# 4_-_Ethernet_PHY.net
KiCad netlist of a schematic drawn in Altium Designer
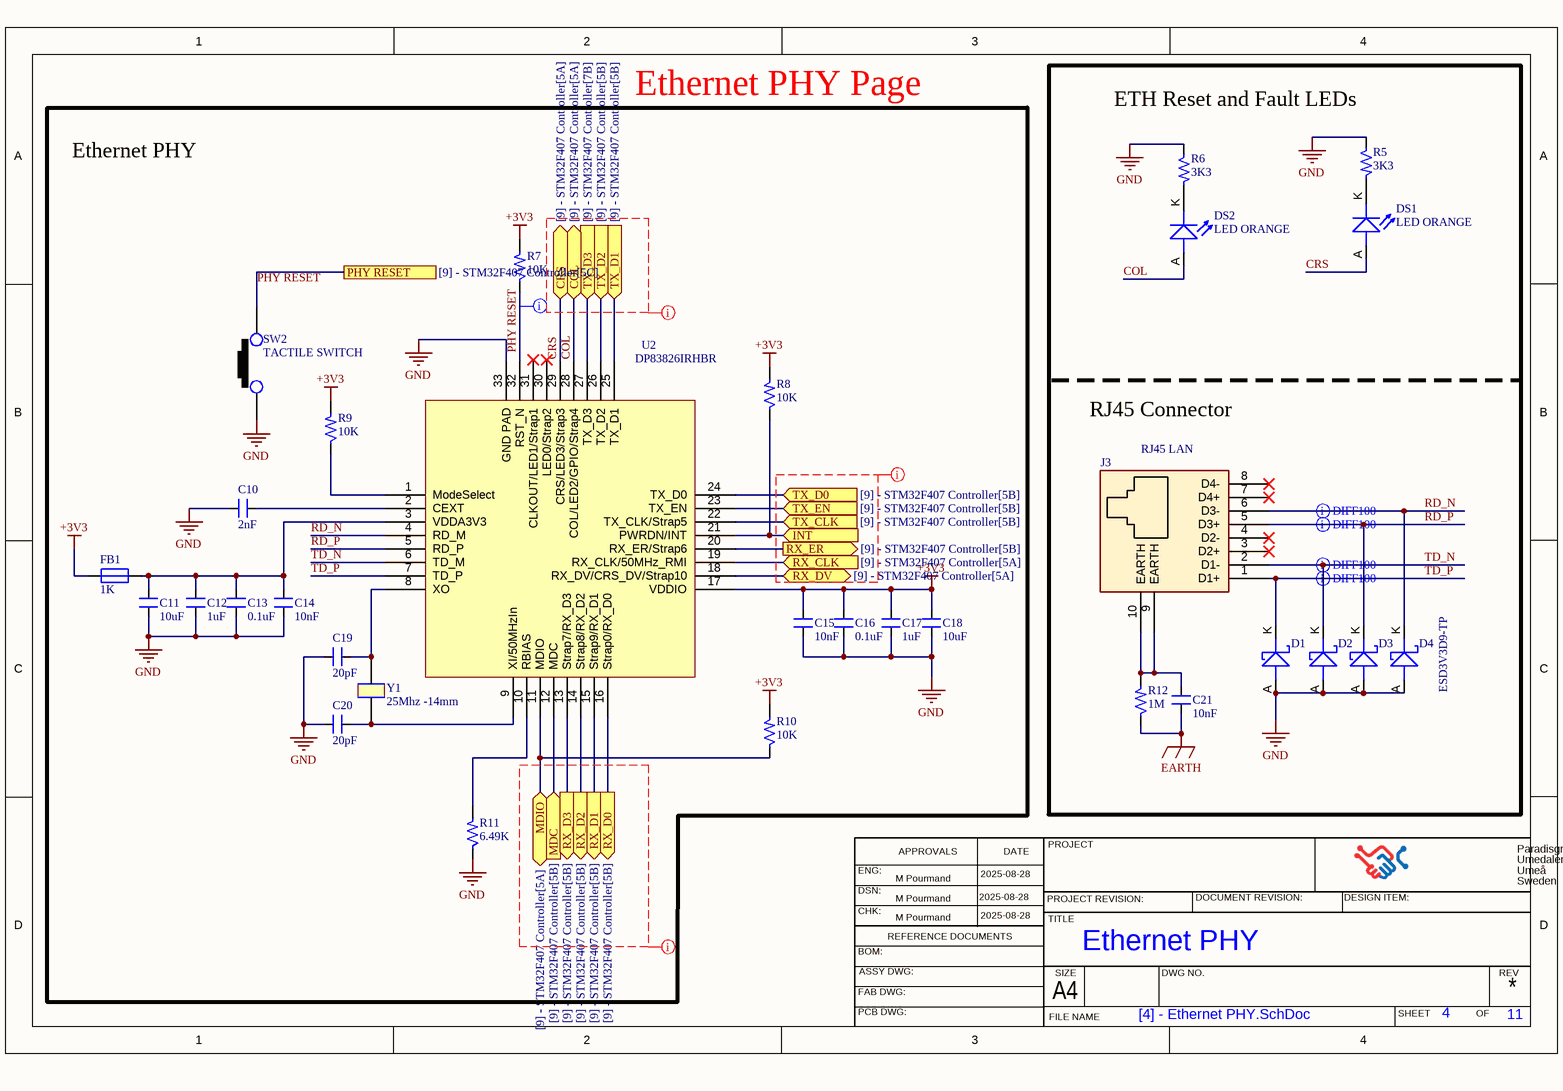
[diagram p0: [4] - Ethernet PHY.SchDoc]

(export (version "E")
  (design (tool "Eeschema 10.0.6"))
  (components
    (comp (ref "C10")
      (value "2nF")
      (footprint "CAP_0805")
      (description "2000pF ±10% 50V Ceramic Capacitor X7R 0805 (2012 Metric)")
      (fields
        (field (name "MANUFACTURER") "Samsung Electro-Mechanics")
        (field (name "MANUFACTURER PART NUMBER") "CL21B202KBANNNC")
      )
      (libsource (lib "ESTEEMPCBLIB") (part "CAP_2nF-50V-10%-0805"))
    )
    (comp (ref "C11")
      (value "10uF")
      (footprint "CAP_1206")
      (description "10µF ±10% 50V Ceramic Capacitor X7R 1206 (3216 Metric)")
      (fields
        (field (name "MANUFACTURER") "KEMET")
        (field (name "MANUFACTURER PART NUMBER") "CL31B106KBHNNNE")
      )
      (libsource (lib "ESTEEMPCBLIB") (part "CAP_10uF-50V-10%-1206"))
    )
    (comp (ref "C12")
      (value "1uF")
      (footprint "CAP_0805")
      (description "1µF ±5% 50V Ceramic Capacitor X7R 0805 (2012 Metric)")
      (fields
        (field (name "MANUFACTURER") "Samsung")
        (field (name "MANUFACTURER PART NUMBER") "CC0805JKX7R9BB105")
      )
      (libsource (lib "ESTEEMPCBLIB") (part "CAP_1uF-50V-5%-0805"))
    )
    (comp (ref "C13")
      (value "0.1uF")
      (footprint "CAP_0805")
      (description "0.1µF ±10% 50V Ceramic Capacitor X7R 0805 (2012 Metric)")
      (fields
        (field (name "MANUFACTURER") "Samsung")
        (field (name "MANUFACTURER PART NUMBER") "CL21B104KBCNNNC")
      )
      (libsource (lib "ESTEEMPCBLIB") (part "CAP_0.1uF-50V-10%-0805"))
    )
    (comp (ref "C14")
      (value "10nF")
      (footprint "CAP_0805")
      (description "10000pF ±10% 50V Ceramic Capacitor X7R 0805 (2012 Metric)")
      (fields
        (field (name "MANUFACTURER") "Samsung")
        (field (name "MANUFACTURER PART NUMBER") "C0805C103K5RECAUTO")
      )
      (libsource (lib "ESTEEMPCBLIB") (part "CAP_10nF-50V-10%-0805"))
    )
    (comp (ref "C15")
      (value "10nF")
      (footprint "CAP_0805")
      (description "10000pF ±10% 50V Ceramic Capacitor X7R 0805 (2012 Metric)")
      (fields
        (field (name "MANUFACTURER") "Samsung")
        (field (name "MANUFACTURER PART NUMBER") "C0805C103K5RECAUTO")
      )
      (libsource (lib "ESTEEMPCBLIB") (part "CAP_10nF-50V-10%-0805"))
    )
    (comp (ref "C16")
      (value "0.1uF")
      (footprint "CAP_0805")
      (description "0.1µF ±10% 50V Ceramic Capacitor X7R 0805 (2012 Metric)")
      (fields
        (field (name "MANUFACTURER") "Samsung")
        (field (name "MANUFACTURER PART NUMBER") "CL21B104KBCNNNC")
      )
      (libsource (lib "ESTEEMPCBLIB") (part "CAP_0.1uF-50V-10%-0805"))
    )
    (comp (ref "C17")
      (value "1uF")
      (footprint "CAP_0805")
      (description "1µF ±5% 50V Ceramic Capacitor X7R 0805 (2012 Metric)")
      (fields
        (field (name "MANUFACTURER") "Samsung")
        (field (name "MANUFACTURER PART NUMBER") "CC0805JKX7R9BB105")
      )
      (libsource (lib "ESTEEMPCBLIB") (part "CAP_1uF-50V-5%-0805"))
    )
    (comp (ref "C18")
      (value "10uF")
      (footprint "CAP_1206")
      (description "10µF ±10% 50V Ceramic Capacitor X7R 1206 (3216 Metric)")
      (fields
        (field (name "MANUFACTURER") "KEMET")
        (field (name "MANUFACTURER PART NUMBER") "CL31B106KBHNNNE")
      )
      (libsource (lib "ESTEEMPCBLIB") (part "CAP_10uF-50V-10%-1206"))
    )
    (comp (ref "C19")
      (value "20pF")
      (footprint "CAP_0805")
      (description "±10% 50V Ceramic Capacitor C0G, NP0 0805 (2012 Metric)")
      (fields
        (field (name "MANUFACTURER") "AVX Corporation")
        (field (name "MANUFACTURER PART NUMBER") "08055A200KAT2A")
      )
      (libsource (lib "ESTEEMPCBLIB") (part "CAP_20pF-50V-10%-0805"))
    )
    (comp (ref "C20")
      (value "20pF")
      (footprint "CAP_0805")
      (description "±10% 50V Ceramic Capacitor C0G, NP0 0805 (2012 Metric)")
      (fields
        (field (name "MANUFACTURER") "AVX Corporation")
        (field (name "MANUFACTURER PART NUMBER") "08055A200KAT2A")
      )
      (libsource (lib "ESTEEMPCBLIB") (part "CAP_20pF-50V-10%-0805"))
    )
    (comp (ref "C21")
      (value "10nF")
      (footprint "CAP_P196_102X287_H332_RAD_TH")
      (description "10000pF ±10% 1000V (1kV) Ceramic Capacitor X7R Radial")
      (fields
        (field (name "MANUFACTURER") "Yageo")
        (field (name "MANUFACTURER PART NUMBER") "RDER73A103K2K1H03B")
      )
      (libsource (lib "ESTEEMPCBLIB") (part "CAP_10nF-1KV-10%-RAD-TH"))
    )
    (comp (ref "D1")
      (value "ESD3V3D9-TP")
      (footprint "DIO_SOD-923")
      (description "8.8V Clamp 5A (8/20µs) Ipp Tvs Diode Surface Mount SOD-923")
      (fields (field (name "MANUFACTURER") "Micro Commercial Co"))
      (libsource (lib "ESTEEMPCBLIB") (part "DIO-T_3.3V-8.8V-SOD923"))
    )
    (comp (ref "D2")
      (value "ESD3V3D9-TP")
      (footprint "DIO_SOD-923")
      (description "8.8V Clamp 5A (8/20µs) Ipp Tvs Diode Surface Mount SOD-923")
      (fields (field (name "MANUFACTURER") "Micro Commercial Co"))
      (libsource (lib "ESTEEMPCBLIB") (part "DIO-T_3.3V-8.8V-SOD923"))
    )
    (comp (ref "D3")
      (value "ESD3V3D9-TP")
      (footprint "DIO_SOD-923")
      (description "8.8V Clamp 5A (8/20µs) Ipp Tvs Diode Surface Mount SOD-923")
      (fields (field (name "MANUFACTURER") "Micro Commercial Co"))
      (libsource (lib "ESTEEMPCBLIB") (part "DIO-T_3.3V-8.8V-SOD923"))
    )
    (comp (ref "D4")
      (value "ESD3V3D9-TP")
      (footprint "DIO_SOD-923")
      (description "8.8V Clamp 5A (8/20µs) Ipp Tvs Diode Surface Mount SOD-923")
      (fields (field (name "MANUFACTURER") "Micro Commercial Co"))
      (libsource (lib "ESTEEMPCBLIB") (part "DIO-T_3.3V-8.8V-SOD923"))
    )
    (comp (ref "DS1")
      (value "LED ORANGE")
      (footprint "LED_0805")
      (description "Orange 605nm LED Indication - Discrete 2V 0805 (2012 Metric)")
      (fields
        (field (name "MANUFACTURER") "Vishay Lite-On")
        (field (name "MANUFACTURER PART NUMBER") "LTST-C170KFKT")
      )
      (libsource (lib "ESTEEMPCBLIB") (part "LED_ORANGE-2V-20mA-0805"))
    )
    (comp (ref "DS2")
      (value "LED ORANGE")
      (footprint "LED_0805")
      (description "Orange 605nm LED Indication - Discrete 2V 0805 (2012 Metric)")
      (fields
        (field (name "MANUFACTURER") "Vishay Lite-On")
        (field (name "MANUFACTURER PART NUMBER") "LTST-C170KFKT")
      )
      (libsource (lib "ESTEEMPCBLIB") (part "LED_ORANGE-2V-20mA-0805"))
    )
    (comp (ref "FB1")
      (value "1K")
      (footprint "IND_0805")
      (description "1 kOhms @ 100MHz 1 Power Line Ferrite Bead 0805 (2012 Metric) 1.6A")
      (fields
        (field (name "MANUFACTURER") "Laird")
        (field (name "MANUFACTURER PART NUMBER") "BLM21SP102SH1D")
      )
      (libsource (lib "ESTEEMPCBLIB") (part "FB_1K-100MHZ-1.6A-0805"))
    )
    (comp (ref "J3")
      (value "RJ45 LAN")
      (footprint "CON10_P106_RJ45_TH_ST")
      (description "8 Pins, 2 Row 2.54mm Pitch, right angle Connector, male")
      (fields
        (field (name "MANUFACTURER") "Assmann")
        (field (name "MANUFACTURER PART NUMBER") "A-2004-2-4-LPS-N-R")
      )
      (libsource (lib "ESTEEMPCBLIB") (part "CON-SKT-RJ_8C8P-RA-TH"))
    )
    (comp (ref "R5")
      (value "3K3")
      (footprint "RES_0603")
      (description "3.3 kOhms ±1% 0.1W, 1/10W Chip Resistor 0603 (1608 Metric) Automotive AEC-Q200 Thick Film")
      (fields (field (name "MANUFACTURER") "Wilson") (field (name "MANUFACTURER PART NUMBER") "WR06X3301FTL"))
      (libsource (lib "ESTEEMPCBLIB") (part "RES_3.3K-0.1W-1%-0603"))
    )
    (comp (ref "R6")
      (value "3K3")
      (footprint "RES_0603")
      (description "3.3 kOhms ±1% 0.1W, 1/10W Chip Resistor 0603 (1608 Metric) Automotive AEC-Q200 Thick Film")
      (fields (field (name "MANUFACTURER") "Wilson") (field (name "MANUFACTURER PART NUMBER") "WR06X3301FTL"))
      (libsource (lib "ESTEEMPCBLIB") (part "RES_3.3K-0.1W-1%-0603"))
    )
    (comp (ref "R7")
      (value "10K")
      (footprint "RES_0603")
      (description "10 kOhms ±1% 0.1W, 1/10W Chip Resistor 0603 (1608 Metric) Automotive AEC-Q200 Thick Film")
      (fields (field (name "MANUFACTURER") "Walsin") (field (name "MANUFACTURER PART NUMBER") "WR06X1002FTL"))
      (libsource (lib "ESTEEMPCBLIB") (part "RES_10K-0.1W-1%-0603"))
    )
    (comp (ref "R8")
      (value "10K")
      (footprint "RES_0603")
      (description "10 kOhms ±1% 0.1W, 1/10W Chip Resistor 0603 (1608 Metric) Automotive AEC-Q200 Thick Film")
      (fields (field (name "MANUFACTURER") "Walsin") (field (name "MANUFACTURER PART NUMBER") "WR06X1002FTL"))
      (libsource (lib "ESTEEMPCBLIB") (part "RES_10K-0.1W-1%-0603"))
    )
    (comp (ref "R9")
      (value "10K")
      (footprint "RES_0603")
      (description "10 kOhms ±1% 0.1W, 1/10W Chip Resistor 0603 (1608 Metric) Automotive AEC-Q200 Thick Film")
      (fields (field (name "MANUFACTURER") "Walsin") (field (name "MANUFACTURER PART NUMBER") "WR06X1002FTL"))
      (libsource (lib "ESTEEMPCBLIB") (part "RES_10K-0.1W-1%-0603"))
    )
    (comp (ref "R10")
      (value "10K")
      (footprint "RES_0603")
      (description "10 kOhms ±1% 0.1W, 1/10W Chip Resistor 0603 (1608 Metric) Automotive AEC-Q200 Thick Film")
      (fields (field (name "MANUFACTURER") "Walsin") (field (name "MANUFACTURER PART NUMBER") "WR06X1002FTL"))
      (libsource (lib "ESTEEMPCBLIB") (part "RES_10K-0.1W-1%-0603"))
    )
    (comp (ref "R11")
      (value "6.49K")
      (footprint "RES_0805")
      (description "6.49 kOhms ±1% 0.125W, 1/8W Chip Resistor 0805 (2012 Metric) Moisture Resistant Thick Film")
      (fields
        (field (name "MANUFACTURER") "Stackpole Electronics")
        (field (name "MANUFACTURER PART NUMBER") "RC0805FR-076K49L")
      )
      (libsource (lib "ESTEEMPCBLIB") (part "RES_6.49K-0.125W-1%-0805"))
    )
    (comp (ref "R12")
      (value "1M")
      (footprint "RES_1206")
      (fields (field (name "MANUFACTURER") "Walsin") (field (name "MANUFACTURER PART NUMBER") "WR12X1004FTL"))
      (libsource (lib "ESTEEMPCBLIB") (part "RES_1M-0.25W-1%-1206"))
    )
    (comp (ref "SW2")
      (value "TACTILE SWITCH")
      (footprint "SW_342_SMD")
      (description "Tactile Switch SPST-NO Top Actuated Surface Mount")
      (fields
        (field (name "MANUFACTURER") "ITT C&K")
        (field (name "MANUFACTURER PART NUMBER") "RS-282G05A3-SMRT")
      )
      (libsource (lib "ESTEEMPCBLIB") (part "SW1_RS-282G05A3-SMRT-SMD"))
    )
    (comp (ref "U2")
      (value "DP83826IRHBR")
      (footprint "VQFN32_19_218_23X9_SMD")
      (fields (field (name "MANUFACTURER") "Texas Instruments"))
      (libsource (lib "ESTEEMPCBLIB") (part "IC_DP83826IRHBR"))
    )
    (comp (ref "Y1")
      (value "25Mhz -14mm")
      (footprint "XTAL_314_240X47_SMD")
      (description "25MHz ±30ppm Crystal 20pF 30 Ohms HC-49/US")
      (fields
        (field (name "MANUFACTURER") "Abracon")
        (field (name "MANUFACTURER PART NUMBER") "FOXSDLF/250F-20")
      )
      (libsource (lib "ESTEEMPCBLIB") (part "XTAL_25Mhz-FOXSDLF/250F-20"))
    )
  )
  (nets
    (net (code "1") (name "+3V3") (class "Default")
      (node (ref "C15") (pin "2") (pinfunction "2_2") (pintype "passive"))
      (node (ref "C16") (pin "2") (pinfunction "2_2") (pintype "passive"))
      (node (ref "C17") (pin "2") (pinfunction "2_2") (pintype "passive"))
      (node (ref "C18") (pin "2") (pinfunction "2_2") (pintype "passive"))
      (node (ref "FB1") (pin "1") (pinfunction "1_1") (pintype "passive"))
      (node (ref "R10") (pin "2") (pinfunction "2_2") (pintype "passive"))
      (node (ref "R7") (pin "2") (pinfunction "2_2") (pintype "passive"))
      (node (ref "R8") (pin "2") (pinfunction "2_2") (pintype "passive"))
      (node (ref "R9") (pin "2") (pinfunction "2_2") (pintype "passive"))
      (node (ref "U2") (pin "17") (pinfunction "VDDIO_17") (pintype "passive"))
    )
    (net (code "2") (name "/COL") (class "Default")
      (node (ref "DS2") (pin "A") (pinfunction "ANODE_A") (pintype "passive"))
      (node (ref "U2") (pin "28") (pinfunction "COL/LED2/GPIO/Strap4_28") (pintype "passive"))
    )
    (net (code "3") (name "/CRS") (class "Default")
      (node (ref "DS1") (pin "A") (pinfunction "ANODE_A") (pintype "passive"))
      (node (ref "U2") (pin "29") (pinfunction "CRS/LED3/Strap3_29") (pintype "passive"))
    )
    (net (code "4") (name "/INT") (class "Default")
      (node (ref "R8") (pin "1") (pinfunction "1_1") (pintype "passive"))
      (node (ref "U2") (pin "21") (pinfunction "PWRDN/INT_21") (pintype "passive"))
    )
    (net (code "5") (name "/MDC") (class "Default")
      (node (ref "U2") (pin "12") (pinfunction "MDC_12") (pintype "passive"))
    )
    (net (code "6") (name "/MDIO") (class "Default")
      (node (ref "R10") (pin "1") (pinfunction "1_1") (pintype "passive"))
      (node (ref "U2") (pin "11") (pinfunction "MDIO_11") (pintype "passive"))
    )
    (net (code "7") (name "/PHY RESET") (class "Default")
      (node (ref "R7") (pin "1") (pinfunction "1_1") (pintype "passive"))
      (node (ref "SW2") (pin "2") (pinfunction "2_2") (pintype "passive"))
      (node (ref "U2") (pin "32") (pinfunction "RST_N_32") (pintype "passive"))
    )
    (net (code "8") (name "/RD_N") (class "Default")
      (node (ref "D4") (pin "K") (pinfunction "K_K") (pintype "passive"))
      (node (ref "J3") (pin "6") (pinfunction "D3-_6") (pintype "passive"))
      (node (ref "U2") (pin "4") (pinfunction "RD_M_4") (pintype "passive"))
    )
    (net (code "9") (name "/RD_P") (class "Default")
      (node (ref "D3") (pin "K") (pinfunction "K_K") (pintype "passive"))
      (node (ref "J3") (pin "5") (pinfunction "D3+_5") (pintype "passive"))
      (node (ref "U2") (pin "5") (pinfunction "RD_P_5") (pintype "passive"))
    )
    (net (code "10") (name "/RX_CLK") (class "Default")
      (node (ref "U2") (pin "19") (pinfunction "RX_CLK/50MHz_RMI_19") (pintype "passive"))
    )
    (net (code "11") (name "/RX_D0") (class "Default")
      (node (ref "U2") (pin "16") (pinfunction "Strap0/RX_D0_16") (pintype "passive"))
    )
    (net (code "12") (name "/RX_D1") (class "Default")
      (node (ref "U2") (pin "15") (pinfunction "Strap9/RX_D1_15") (pintype "passive"))
    )
    (net (code "13") (name "/RX_D2") (class "Default")
      (node (ref "U2") (pin "14") (pinfunction "Strap8/RX_D2_14") (pintype "passive"))
    )
    (net (code "14") (name "/RX_D3") (class "Default")
      (node (ref "U2") (pin "13") (pinfunction "Strap7/RX_D3_13") (pintype "passive"))
    )
    (net (code "15") (name "/RX_DV") (class "Default")
      (node (ref "U2") (pin "18") (pinfunction "RX_DV/CRS_DV/Strap10_18") (pintype "passive"))
    )
    (net (code "16") (name "/RX_ER") (class "Default")
      (node (ref "U2") (pin "20") (pinfunction "RX_ER/Strap6_20") (pintype "passive"))
    )
    (net (code "17") (name "/TD_N") (class "Default")
      (node (ref "D2") (pin "K") (pinfunction "K_K") (pintype "passive"))
      (node (ref "J3") (pin "2") (pinfunction "D1-_2") (pintype "passive"))
      (node (ref "U2") (pin "6") (pinfunction "TD_M_6") (pintype "passive"))
    )
    (net (code "18") (name "/TD_P") (class "Default")
      (node (ref "D1") (pin "K") (pinfunction "K_K") (pintype "passive"))
      (node (ref "J3") (pin "1") (pinfunction "D1+_1") (pintype "passive"))
      (node (ref "U2") (pin "7") (pinfunction "TD_P_7") (pintype "passive"))
    )
    (net (code "19") (name "/TX_CLK") (class "Default")
      (node (ref "U2") (pin "22") (pinfunction "TX_CLK/Strap5_22") (pintype "passive"))
    )
    (net (code "20") (name "/TX_D0") (class "Default")
      (node (ref "U2") (pin "24") (pinfunction "TX_D0_24") (pintype "passive"))
    )
    (net (code "21") (name "/TX_D1") (class "Default")
      (node (ref "U2") (pin "25") (pinfunction "TX_D1_25") (pintype "passive"))
    )
    (net (code "22") (name "/TX_D2") (class "Default")
      (node (ref "U2") (pin "26") (pinfunction "TX_D2_26") (pintype "passive"))
    )
    (net (code "23") (name "/TX_D3") (class "Default")
      (node (ref "U2") (pin "27") (pinfunction "TX_D3_27") (pintype "passive"))
    )
    (net (code "24") (name "/TX_EN") (class "Default")
      (node (ref "U2") (pin "23") (pinfunction "TX_EN_23") (pintype "passive"))
    )
    (net (code "25") (name "EARTH") (class "Default")
      (node (ref "C21") (pin "1") (pinfunction "1_1") (pintype "passive"))
      (node (ref "R12") (pin "1") (pinfunction "1_1") (pintype "passive"))
    )
    (net (code "26") (name "GND") (class "Default")
      (node (ref "C10") (pin "1") (pinfunction "1_1") (pintype "passive"))
      (node (ref "C11") (pin "1") (pinfunction "1_1") (pintype "passive"))
      (node (ref "C12") (pin "1") (pinfunction "1_1") (pintype "passive"))
      (node (ref "C13") (pin "1") (pinfunction "1_1") (pintype "passive"))
      (node (ref "C14") (pin "1") (pinfunction "1_1") (pintype "passive"))
      (node (ref "C15") (pin "1") (pinfunction "1_1") (pintype "passive"))
      (node (ref "C16") (pin "1") (pinfunction "1_1") (pintype "passive"))
      (node (ref "C17") (pin "1") (pinfunction "1_1") (pintype "passive"))
      (node (ref "C18") (pin "1") (pinfunction "1_1") (pintype "passive"))
      (node (ref "C19") (pin "2") (pinfunction "2_2") (pintype "passive"))
      (node (ref "C20") (pin "2") (pinfunction "2_2") (pintype "passive"))
      (node (ref "D1") (pin "A") (pinfunction "A_A") (pintype "passive"))
      (node (ref "D2") (pin "A") (pinfunction "A_A") (pintype "passive"))
      (node (ref "D3") (pin "A") (pinfunction "A_A") (pintype "passive"))
      (node (ref "D4") (pin "A") (pinfunction "A_A") (pintype "passive"))
      (node (ref "R11") (pin "1") (pinfunction "1_1") (pintype "passive"))
      (node (ref "R5") (pin "1") (pinfunction "1_1") (pintype "passive"))
      (node (ref "R6") (pin "1") (pinfunction "1_1") (pintype "passive"))
      (node (ref "SW2") (pin "1") (pinfunction "1_1") (pintype "passive"))
      (node (ref "U2") (pin "33") (pinfunction "GND_PAD_33") (pintype "passive"))
    )
    (net (code "27") (name "Net-(C21-Pad2)") (class "Default")
      (node (ref "C21") (pin "2") (pinfunction "2_2") (pintype "passive"))
      (node (ref "J3") (pin "10") (pinfunction "EARTH_10") (pintype "passive"))
      (node (ref "J3") (pin "9") (pinfunction "EARTH_9") (pintype "passive"))
      (node (ref "R12") (pin "2") (pinfunction "2_2") (pintype "passive"))
    )
    (net (code "28") (name "Net-(DS1-CATHODE)") (class "Default")
      (node (ref "DS1") (pin "K") (pinfunction "CATHODE_K") (pintype "passive"))
      (node (ref "R5") (pin "2") (pinfunction "2_2") (pintype "passive"))
    )
    (net (code "29") (name "Net-(DS2-CATHODE)") (class "Default")
      (node (ref "DS2") (pin "K") (pinfunction "CATHODE_K") (pintype "passive"))
      (node (ref "R6") (pin "2") (pinfunction "2_2") (pintype "passive"))
    )
    (net (code "30") (name "Net-(U2-CEXT)") (class "Default")
      (node (ref "C10") (pin "2") (pinfunction "2_2") (pintype "passive"))
      (node (ref "U2") (pin "2") (pinfunction "CEXT_2") (pintype "passive"))
    )
    (net (code "31") (name "Net-(U2-ModeSelect)") (class "Default")
      (node (ref "R9") (pin "1") (pinfunction "1_1") (pintype "passive"))
      (node (ref "U2") (pin "1") (pinfunction "ModeSelect_1") (pintype "passive"))
    )
    (net (code "32") (name "Net-(U2-RBIAS)") (class "Default")
      (node (ref "R11") (pin "2") (pinfunction "2_2") (pintype "passive"))
      (node (ref "U2") (pin "10") (pinfunction "RBIAS_10") (pintype "passive"))
    )
    (net (code "33") (name "Net-(U2-VDDA3V3)") (class "Default")
      (node (ref "C11") (pin "2") (pinfunction "2_2") (pintype "passive"))
      (node (ref "C12") (pin "2") (pinfunction "2_2") (pintype "passive"))
      (node (ref "C13") (pin "2") (pinfunction "2_2") (pintype "passive"))
      (node (ref "C14") (pin "2") (pinfunction "2_2") (pintype "passive"))
      (node (ref "FB1") (pin "2") (pinfunction "2_2") (pintype "passive"))
      (node (ref "U2") (pin "3") (pinfunction "VDDA3V3_3") (pintype "passive"))
    )
    (net (code "34") (name "Net-(U2-XI{slash}50MHzIn)") (class "Default")
      (node (ref "C20") (pin "1") (pinfunction "1_1") (pintype "passive"))
      (node (ref "U2") (pin "9") (pinfunction "XI/50MHzIn_9") (pintype "passive"))
      (node (ref "Y1") (pin "1") (pinfunction "1_1") (pintype "passive"))
    )
    (net (code "35") (name "Net-(U2-XO)") (class "Default")
      (node (ref "C19") (pin "1") (pinfunction "1_1") (pintype "passive"))
      (node (ref "U2") (pin "8") (pinfunction "XO_8") (pintype "passive"))
      (node (ref "Y1") (pin "2") (pinfunction "2_2") (pintype "passive"))
    )
    (net (code "36") (name "unconnected-(J3-D2+-Pad3)") (class "Default")
      (node (ref "J3") (pin "3") (pinfunction "D2+_3") (pintype "passive+no_connect"))
    )
    (net (code "37") (name "unconnected-(J3-D2--Pad4)") (class "Default")
      (node (ref "J3") (pin "4") (pinfunction "D2-_4") (pintype "passive+no_connect"))
    )
    (net (code "38") (name "unconnected-(J3-D4+-Pad7)") (class "Default")
      (node (ref "J3") (pin "7") (pinfunction "D4+_7") (pintype "passive+no_connect"))
    )
    (net (code "39") (name "unconnected-(J3-D4--Pad8)") (class "Default")
      (node (ref "J3") (pin "8") (pinfunction "D4-_8") (pintype "passive+no_connect"))
    )
    (net (code "40") (name "unconnected-(U2-CLKOUT{slash}LED1{slash}Strap1-Pad31)") (class "Default")
      (node (ref "U2") (pin "31") (pinfunction "CLKOUT/LED1/Strap1_31") (pintype "passive+no_connect"))
    )
    (net (code "41") (name "unconnected-(U2-LED0{slash}Strap2-Pad30)") (class "Default")
      (node (ref "U2") (pin "30") (pinfunction "LED0/Strap2_30") (pintype "passive+no_connect"))
    )
  )
)
